# Sheet1.net
KiCad netlist of a schematic drawn in Altium Designer
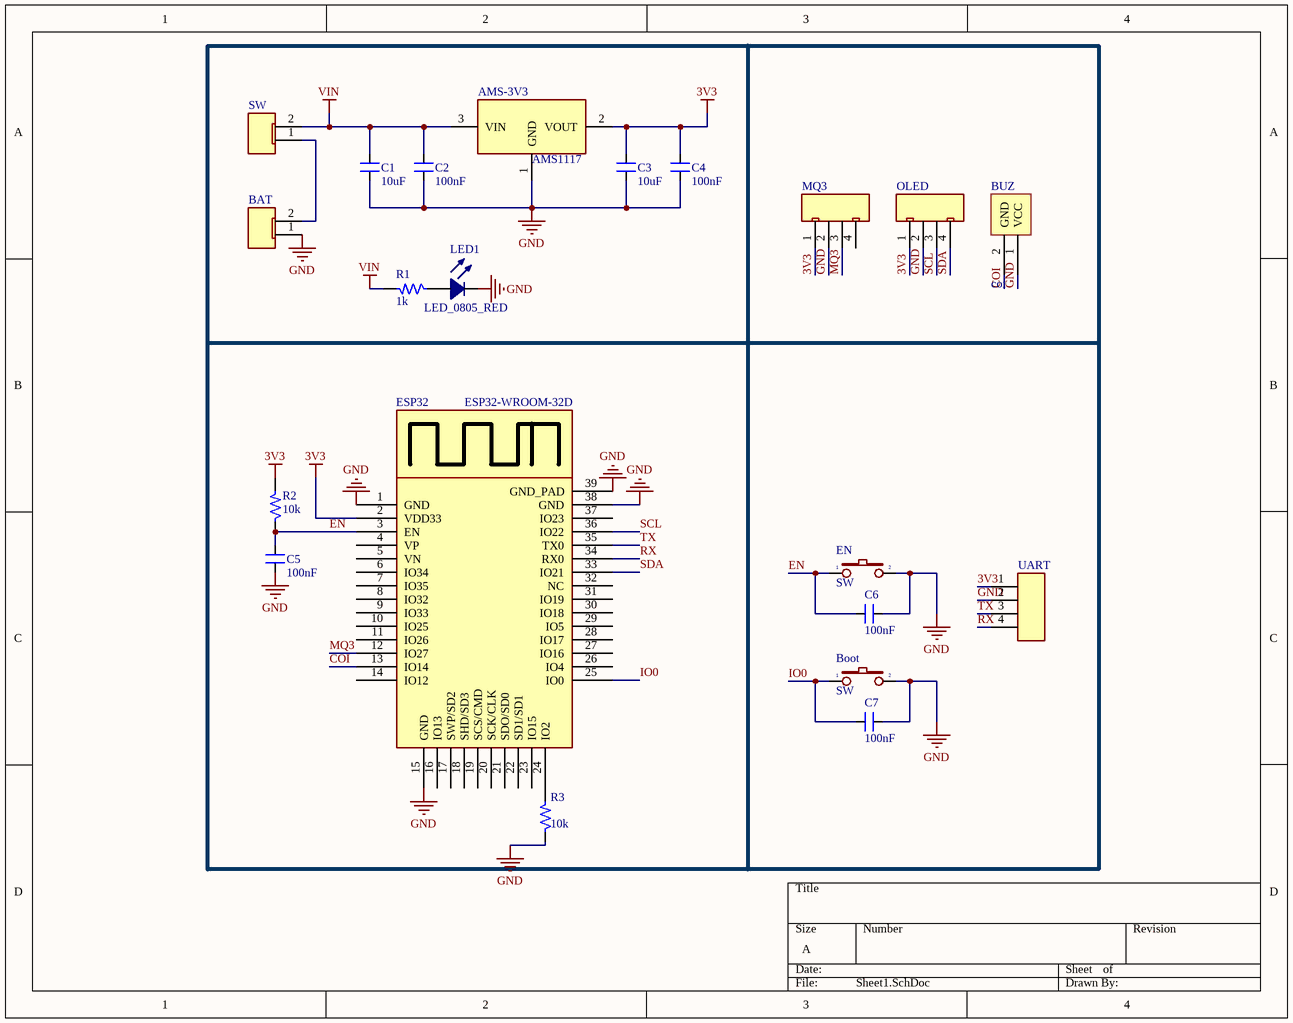
[diagram p0: Sheet1.SchDoc]

(export (version "E")
  (design (tool "Eeschema 10.0.6"))
  (components
    (comp (ref "AMS-3V3")
      (value "AMS1117")
      (footprint "AMS1117")
      (description "IC REG LINEAR 1A SOT-89-3L")
      (libsource (lib "Voltage Regulators") (part "AMS1117"))
    )
    (comp (ref "BAT")
      (value "JST-2.00-2P")
      (footprint "JST-2.00-2P")
      (description "Female Connector JST 2 Vias, 2.00mm.")
      (libsource (lib "Connectors") (part "JST-2.00-2P"))
    )
    (comp (ref "Boot")
      (value "SW")
      (footprint "SW2")
      (description "Switch button 2 pin")
      (libsource (lib "syhaunguyen") (part "SW2"))
    )
    (comp (ref "BUZ") (value "coi") (footprint "Buzzer") (libsource (lib "LeDucTuan") (part "COI SFM27")))
    (comp (ref "C1")
      (value "10uF")
      (footprint "SM-1206")
      (description "Cap SMD")
      (libsource (lib "syhaunguyen") (part "CM"))
    )
    (comp (ref "C2")
      (value "100nF")
      (footprint "SM-1206")
      (description "Cap SMD")
      (libsource (lib "syhaunguyen") (part "CM"))
    )
    (comp (ref "C3")
      (value "10uF")
      (footprint "SM-1206")
      (description "Cap SMD")
      (libsource (lib "syhaunguyen") (part "CM"))
    )
    (comp (ref "C4")
      (value "100nF")
      (footprint "SM-1206")
      (description "Cap SMD")
      (libsource (lib "syhaunguyen") (part "CM"))
    )
    (comp (ref "C5")
      (value "100nF")
      (footprint "SM-1206")
      (description "Cap SMD")
      (libsource (lib "syhaunguyen") (part "CM"))
    )
    (comp (ref "C6")
      (value "100nF")
      (footprint "SM-1206")
      (description "Cap SMD")
      (libsource (lib "syhaunguyen") (part "CM"))
    )
    (comp (ref "C7")
      (value "100nF")
      (footprint "SM-1206")
      (description "Cap SMD")
      (libsource (lib "syhaunguyen") (part "CM"))
    )
    (comp (ref "EN")
      (value "SW")
      (footprint "SW2")
      (description "Switch button 2 pin")
      (libsource (lib "syhaunguyen") (part "SW2"))
    )
    (comp (ref "ESP32")
      (value "ESP32-WROOM-32D")
      (footprint "ESP32-WROOM-32D")
      (description "Chip SMD 39 Pads Wifi 2.4GHz BLE 4.2 18x25.5mm w/ Antenna.")
      (libsource (lib "Espressif Microcontrollers") (part "ESP32-WROOM-32D"))
    )
    (comp (ref "LED1")
      (value "LED_0805_RED")
      (footprint "LED_0805_RED")
      (description "LED 0805 Red.")
      (libsource (lib "LED") (part "LED_0805_RED"))
    )
    (comp (ref "MQ3")
      (value "JST-2.00-4P")
      (footprint "JST-2.00-4P")
      (description "Female Connector JST 4 Vias, 2.00mm.")
      (libsource (lib "Connectors") (part "JST-2.00-4P"))
    )
    (comp (ref "OLED")
      (value "JST-2.00-4P")
      (footprint "JST-2.00-4P")
      (description "Female Connector JST 4 Vias, 2.00mm.")
      (libsource (lib "Connectors") (part "JST-2.00-4P"))
    )
    (comp (ref "R1")
      (value "1k")
      (footprint "SM-1206")
      (description "Resistor 1/4W")
      (libsource (lib "syhaunguyen") (part "R"))
    )
    (comp (ref "R2")
      (value "10k")
      (footprint "SM-1206")
      (description "Resistor 1/4W")
      (libsource (lib "syhaunguyen") (part "R"))
    )
    (comp (ref "R3")
      (value "10k")
      (footprint "SM-1206")
      (description "Resistor 1/4W")
      (libsource (lib "syhaunguyen") (part "R"))
    )
    (comp (ref "SW")
      (value "JST-2.00-2P")
      (footprint "JST-2.00-2P")
      (description "Female Connector JST 2 Vias, 2.00mm.")
      (libsource (lib "Connectors") (part "JST-2.00-2P"))
    )
    (comp (ref "UART")
      (value "MALE-2.54-4P")
      (footprint "MALE-2.54-4P")
      (description "Male Header Connector 2.54mm 4 Pins.")
      (libsource (lib "Connectors") (part "MALE-2.54-4P"))
    )
  )
  (nets
    (net (code "1") (name "/COI") (class "Default")
      (node (ref "BUZ") (pin "2") (pinfunction "GND_2") (pintype "passive"))
      (node (ref "ESP32") (pin "13") (pinfunction "IO14_13") (pintype "passive"))
    )
    (net (code "2") (name "/EN") (class "Default")
      (node (ref "C5") (pin "1") (pinfunction "1_1") (pintype "passive"))
      (node (ref "C6") (pin "2") (pinfunction "2_2") (pintype "passive"))
      (node (ref "EN") (pin "1") (pinfunction "1_1") (pintype "passive"))
      (node (ref "ESP32") (pin "3") (pinfunction "EN_3") (pintype "passive"))
      (node (ref "R2") (pin "1") (pinfunction "1_1") (pintype "passive"))
    )
    (net (code "3") (name "/IO0") (class "Default")
      (node (ref "Boot") (pin "1") (pinfunction "1_1") (pintype "passive"))
      (node (ref "C7") (pin "2") (pinfunction "2_2") (pintype "passive"))
      (node (ref "ESP32") (pin "25") (pinfunction "IO0_25") (pintype "passive"))
    )
    (net (code "4") (name "/MQ3") (class "Default")
      (node (ref "ESP32") (pin "12") (pinfunction "IO27_12") (pintype "passive"))
      (node (ref "MQ3") (pin "3") (pintype "passive"))
    )
    (net (code "5") (name "/RX") (class "Default")
      (node (ref "ESP32") (pin "34") (pinfunction "RX0_34") (pintype "passive"))
      (node (ref "UART") (pin "4") (pintype "passive"))
    )
    (net (code "6") (name "/SCL") (class "Default")
      (node (ref "ESP32") (pin "36") (pinfunction "IO22_36") (pintype "passive"))
      (node (ref "OLED") (pin "3") (pintype "passive"))
    )
    (net (code "7") (name "/SDA") (class "Default")
      (node (ref "ESP32") (pin "33") (pinfunction "IO21_33") (pintype "passive"))
      (node (ref "OLED") (pin "4") (pintype "passive"))
    )
    (net (code "8") (name "/TX") (class "Default")
      (node (ref "ESP32") (pin "35") (pinfunction "TX0_35") (pintype "passive"))
      (node (ref "UART") (pin "3") (pintype "passive"))
    )
    (net (code "9") (name "3V3") (class "Default")
      (node (ref "AMS-3V3") (pin "2") (pinfunction "VOUT_2") (pintype "passive"))
      (node (ref "C3") (pin "1") (pinfunction "1_1") (pintype "passive"))
      (node (ref "C4") (pin "1") (pinfunction "1_1") (pintype "passive"))
      (node (ref "ESP32") (pin "2") (pinfunction "VDD33_2") (pintype "passive"))
      (node (ref "MQ3") (pin "1") (pintype "passive"))
      (node (ref "OLED") (pin "1") (pintype "passive"))
      (node (ref "R2") (pin "2") (pinfunction "2_2") (pintype "passive"))
      (node (ref "UART") (pin "1") (pintype "passive"))
    )
    (net (code "10") (name "GND") (class "Default")
      (node (ref "AMS-3V3") (pin "1") (pinfunction "GND_1") (pintype "passive"))
      (node (ref "BAT") (pin "1") (pintype "passive"))
      (node (ref "BUZ") (pin "1") (pinfunction "VCC_1") (pintype "passive"))
      (node (ref "Boot") (pin "2") (pinfunction "2_2") (pintype "passive"))
      (node (ref "C1") (pin "2") (pinfunction "2_2") (pintype "passive"))
      (node (ref "C2") (pin "2") (pinfunction "2_2") (pintype "passive"))
      (node (ref "C3") (pin "2") (pinfunction "2_2") (pintype "passive"))
      (node (ref "C4") (pin "2") (pinfunction "2_2") (pintype "passive"))
      (node (ref "C5") (pin "2") (pinfunction "2_2") (pintype "passive"))
      (node (ref "C6") (pin "1") (pinfunction "1_1") (pintype "passive"))
      (node (ref "C7") (pin "1") (pinfunction "1_1") (pintype "passive"))
      (node (ref "EN") (pin "2") (pinfunction "2_2") (pintype "passive"))
      (node (ref "ESP32") (pin "1") (pinfunction "GND_1") (pintype "passive"))
      (node (ref "ESP32") (pin "15") (pinfunction "GND_15") (pintype "passive"))
      (node (ref "ESP32") (pin "38") (pinfunction "GND_38") (pintype "passive"))
      (node (ref "ESP32") (pin "39") (pinfunction "GND_PAD_39") (pintype "passive"))
      (node (ref "LED1") (pin "2") (pinfunction "2_2") (pintype "passive"))
      (node (ref "MQ3") (pin "2") (pintype "passive"))
      (node (ref "OLED") (pin "2") (pintype "passive"))
      (node (ref "R3") (pin "1") (pinfunction "1_1") (pintype "passive"))
      (node (ref "UART") (pin "2") (pintype "passive"))
    )
    (net (code "11") (name "Net-(BAT-Pad2)") (class "Default")
      (node (ref "BAT") (pin "2") (pintype "passive"))
      (node (ref "SW") (pin "1") (pintype "passive"))
    )
    (net (code "12") (name "Net-(ESP32-IO2)") (class "Default")
      (node (ref "ESP32") (pin "24") (pinfunction "IO2_24") (pintype "passive"))
      (node (ref "R3") (pin "2") (pinfunction "2_2") (pintype "passive"))
    )
    (net (code "13") (name "Net-(LED1-Pad1)") (class "Default")
      (node (ref "LED1") (pin "1") (pinfunction "1_1") (pintype "passive"))
      (node (ref "R1") (pin "1") (pinfunction "1_1") (pintype "passive"))
    )
    (net (code "14") (name "VIN") (class "Default")
      (node (ref "AMS-3V3") (pin "3") (pinfunction "VIN_3") (pintype "passive"))
      (node (ref "C1") (pin "1") (pinfunction "1_1") (pintype "passive"))
      (node (ref "C2") (pin "1") (pinfunction "1_1") (pintype "passive"))
      (node (ref "R1") (pin "2") (pinfunction "2_2") (pintype "passive"))
      (node (ref "SW") (pin "2") (pintype "passive"))
    )
    (net (code "15") (name "unconnected-(ESP32-IO4-Pad26)") (class "Default")
      (node (ref "ESP32") (pin "26") (pinfunction "IO4_26") (pintype "passive"))
    )
    (net (code "16") (name "unconnected-(ESP32-IO5-Pad29)") (class "Default")
      (node (ref "ESP32") (pin "29") (pinfunction "IO5_29") (pintype "passive"))
    )
    (net (code "17") (name "unconnected-(ESP32-IO12-Pad14)") (class "Default")
      (node (ref "ESP32") (pin "14") (pinfunction "IO12_14") (pintype "passive"))
    )
    (net (code "18") (name "unconnected-(ESP32-IO13-Pad16)") (class "Default")
      (node (ref "ESP32") (pin "16") (pinfunction "IO13_16") (pintype "passive"))
    )
    (net (code "19") (name "unconnected-(ESP32-IO15-Pad23)") (class "Default")
      (node (ref "ESP32") (pin "23") (pinfunction "IO15_23") (pintype "passive"))
    )
    (net (code "20") (name "unconnected-(ESP32-IO16-Pad27)") (class "Default")
      (node (ref "ESP32") (pin "27") (pinfunction "IO16_27") (pintype "passive"))
    )
    (net (code "21") (name "unconnected-(ESP32-IO17-Pad28)") (class "Default")
      (node (ref "ESP32") (pin "28") (pinfunction "IO17_28") (pintype "passive"))
    )
    (net (code "22") (name "unconnected-(ESP32-IO18-Pad30)") (class "Default")
      (node (ref "ESP32") (pin "30") (pinfunction "IO18_30") (pintype "passive"))
    )
    (net (code "23") (name "unconnected-(ESP32-IO19-Pad31)") (class "Default")
      (node (ref "ESP32") (pin "31") (pinfunction "IO19_31") (pintype "passive"))
    )
    (net (code "24") (name "unconnected-(ESP32-IO23-Pad37)") (class "Default")
      (node (ref "ESP32") (pin "37") (pinfunction "IO23_37") (pintype "passive"))
    )
    (net (code "25") (name "unconnected-(ESP32-IO25-Pad10)") (class "Default")
      (node (ref "ESP32") (pin "10") (pinfunction "IO25_10") (pintype "passive"))
    )
    (net (code "26") (name "unconnected-(ESP32-IO26-Pad11)") (class "Default")
      (node (ref "ESP32") (pin "11") (pinfunction "IO26_11") (pintype "passive"))
    )
    (net (code "27") (name "unconnected-(ESP32-IO32-Pad8)") (class "Default")
      (node (ref "ESP32") (pin "8") (pinfunction "IO32_8") (pintype "passive"))
    )
    (net (code "28") (name "unconnected-(ESP32-IO33-Pad9)") (class "Default")
      (node (ref "ESP32") (pin "9") (pinfunction "IO33_9") (pintype "passive"))
    )
    (net (code "29") (name "unconnected-(ESP32-IO34-Pad6)") (class "Default")
      (node (ref "ESP32") (pin "6") (pinfunction "IO34_6") (pintype "passive"))
    )
    (net (code "30") (name "unconnected-(ESP32-IO35-Pad7)") (class "Default")
      (node (ref "ESP32") (pin "7") (pinfunction "IO35_7") (pintype "passive"))
    )
    (net (code "31") (name "unconnected-(ESP32-NC-Pad32)") (class "Default")
      (node (ref "ESP32") (pin "32") (pinfunction "NC_32") (pintype "passive"))
    )
    (net (code "32") (name "unconnected-(ESP32-SCK{slash}CLK-Pad20)") (class "Default")
      (node (ref "ESP32") (pin "20") (pinfunction "SCK/CLK_20") (pintype "passive"))
    )
    (net (code "33") (name "unconnected-(ESP32-SCS{slash}CMD-Pad19)") (class "Default")
      (node (ref "ESP32") (pin "19") (pinfunction "SCS/CMD_19") (pintype "passive"))
    )
    (net (code "34") (name "unconnected-(ESP32-SD1{slash}SD1-Pad22)") (class "Default")
      (node (ref "ESP32") (pin "22") (pinfunction "SD1/SD1_22") (pintype "passive"))
    )
    (net (code "35") (name "unconnected-(ESP32-SDO{slash}SD0-Pad21)") (class "Default")
      (node (ref "ESP32") (pin "21") (pinfunction "SDO/SD0_21") (pintype "passive"))
    )
    (net (code "36") (name "unconnected-(ESP32-SHD{slash}SD3-Pad18)") (class "Default")
      (node (ref "ESP32") (pin "18") (pinfunction "SHD/SD3_18") (pintype "passive"))
    )
    (net (code "37") (name "unconnected-(ESP32-SWP{slash}SD2-Pad17)") (class "Default")
      (node (ref "ESP32") (pin "17") (pinfunction "SWP/SD2_17") (pintype "passive"))
    )
    (net (code "38") (name "unconnected-(ESP32-VN-Pad5)") (class "Default")
      (node (ref "ESP32") (pin "5") (pinfunction "VN_5") (pintype "passive"))
    )
    (net (code "39") (name "unconnected-(ESP32-VP-Pad4)") (class "Default")
      (node (ref "ESP32") (pin "4") (pinfunction "VP_4") (pintype "passive"))
    )
    (net (code "40") (name "unconnected-(MQ3-Pad4)") (class "Default")
      (node (ref "MQ3") (pin "4") (pintype "passive"))
    )
  )
)
